# 2_WiFi_Arduino_Pinout.net
KiCad netlist of a schematic drawn in Altium Designer
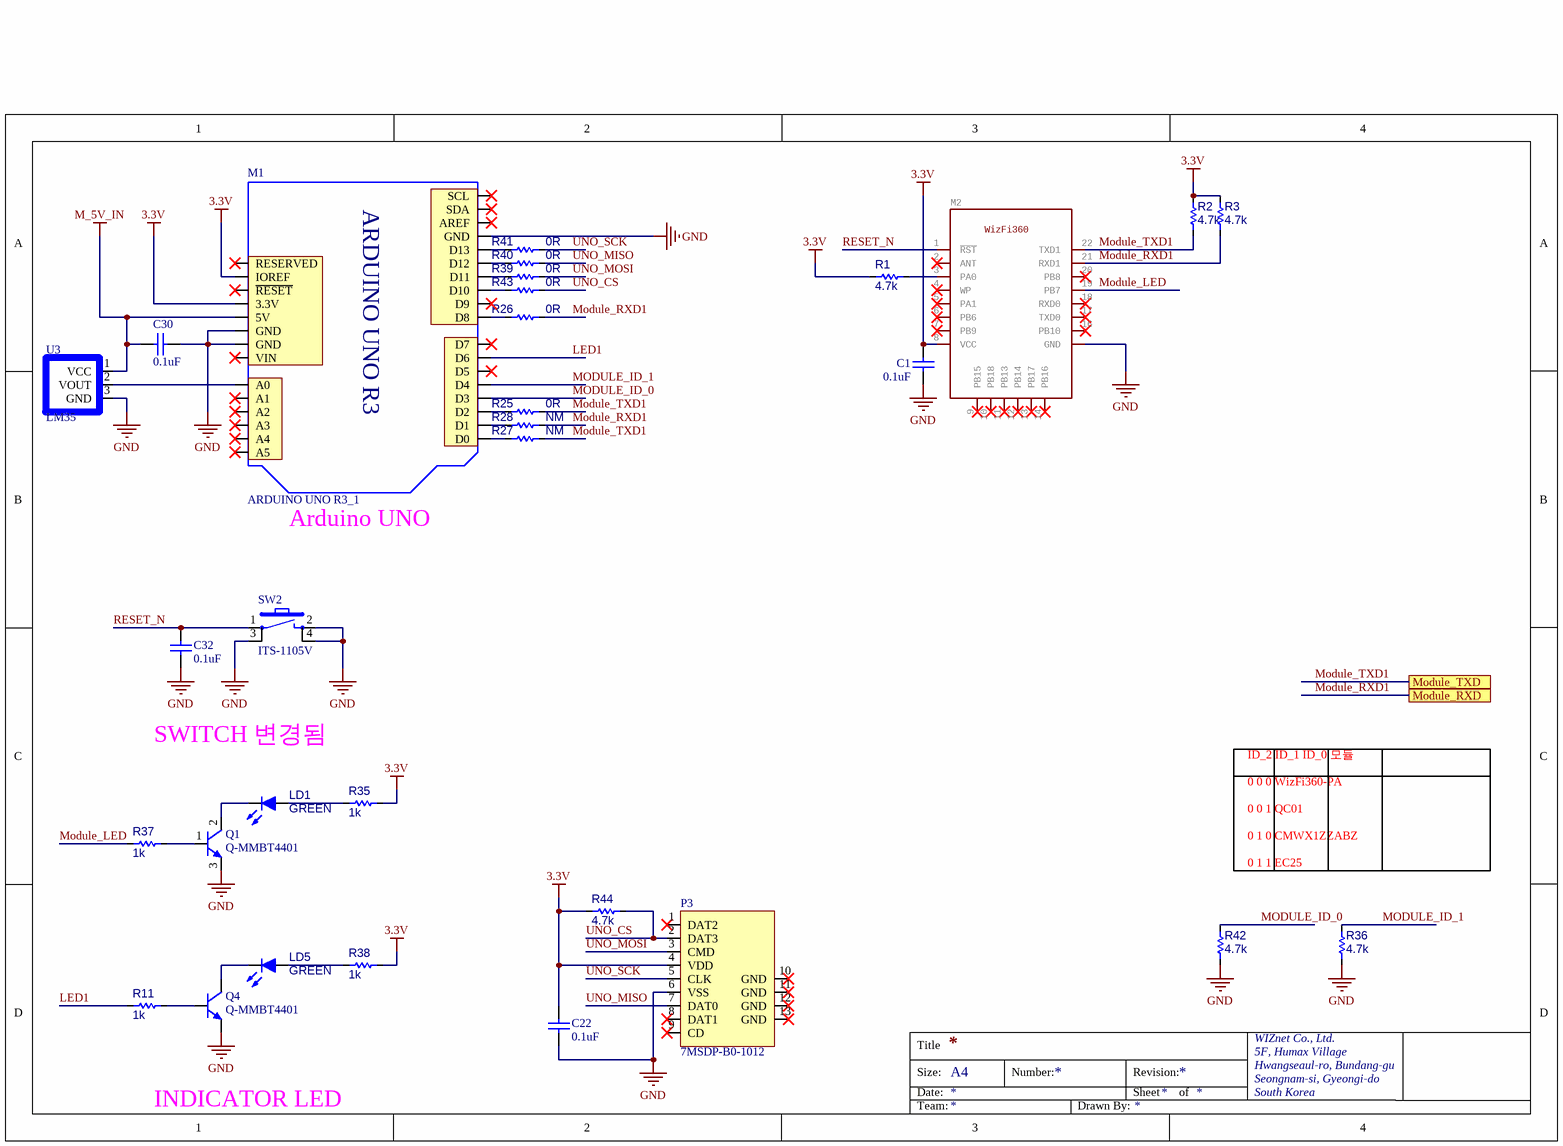
[diagram p0: 2.WiFi_Arduino Pinout.SchDoc]

(export (version "E")
  (design (tool "Eeschema 10.0.6"))
  (components
    (comp (ref "C1")
      (value "0.1uF")
      (footprint "CAP-0402")
      (description "Ceramic CAP 0402(1005)")
      (libsource (lib "Edward") (part "CAP-0402"))
    )
    (comp (ref "C22")
      (value "0.1uF")
      (footprint "CAP-0402")
      (description "Ceramic CAP 0402(1005)")
      (libsource (lib "Edward") (part "CAP-0402"))
    )
    (comp (ref "C30")
      (value "0.1uF")
      (footprint "CAP-0402")
      (description "Ceramic CAP 0402(1005)")
      (libsource (lib "Edward") (part "CAP-0402"))
    )
    (comp (ref "C32")
      (value "0.1uF")
      (footprint "CAP-0402")
      (description "Ceramic CAP 0402(1005)")
      (libsource (lib "Edward") (part "CAP-0402"))
    )
    (comp (ref "LD1")
      (value "GREEN")
      (footprint "LED-0603-GREEN")
      (description "LED-0603")
      (libsource (lib "Scott_lib") (part "LED-0603"))
    )
    (comp (ref "LD5")
      (value "GREEN")
      (footprint "LED-0603-GREEN")
      (description "LED-0603")
      (libsource (lib "Scott_lib") (part "LED-0603"))
    )
    (comp (ref "M1")
      (value "ARDUINO UNO R3_1")
      (footprint "ARDUINOR3_ICSP(3)")
      (description "Arduino UNO R3")
      (libsource (lib "Scott_lib") (part "ARDUINO UNO R3_1"))
    )
    (comp (ref "M2")
      (value "WIZFI360")
      (footprint "WizFi360-PA")
      (fields (field (name "WIZFI360") "WizFi360") (field (name "LIBRARYNAME") "WIZnet"))
      (libsource (lib "WIZnet") (part "WIZFI360"))
    )
    (comp (ref "P3")
      (value "7MSDP-B0-1012")
      (footprint "7MSDP-B0-1012")
      (description "Micro SD Card Socket")
      (libsource (lib "Scott_lib") (part "7MSDP-B0-1012"))
    )
    (comp (ref "Q1")
      (value "Q-MMBT4401")
      (footprint "SOT-23-3LL")
      (description "NPN General-Purpose Amplifier")
      (libsource (lib "Edward") (part "Q-MMBT4401"))
    )
    (comp (ref "Q4")
      (value "Q-MMBT4401")
      (footprint "SOT-23-3LL")
      (description "NPN General-Purpose Amplifier")
      (libsource (lib "") (part "Q-MMBT4401_1"))
    )
    (comp (ref "R1")
      (value "4.7k")
      (footprint "RES-0402")
      (description "RES-0402")
      (libsource (lib "Edward") (part "RES-0402"))
    )
    (comp (ref "R2")
      (value "4.7k")
      (footprint "RES-0402")
      (description "RES-0402")
      (libsource (lib "Edward") (part "RES-0402"))
    )
    (comp (ref "R3")
      (value "4.7k")
      (footprint "RES-0402")
      (description "RES-0402")
      (libsource (lib "Edward") (part "RES-0402"))
    )
    (comp (ref "R11")
      (value "1k")
      (footprint "RES-0402")
      (description "RES-0402")
      (libsource (lib "Edward") (part "RES-0402"))
    )
    (comp (ref "R25")
      (value "0R")
      (footprint "RES-0402")
      (description "RES-0402")
      (libsource (lib "Scott_lib") (part "RES-0402"))
    )
    (comp (ref "R26")
      (value "0R")
      (footprint "RES-0402")
      (description "RES-0402")
      (libsource (lib "Scott_lib") (part "RES-0402"))
    )
    (comp (ref "R27")
      (value "NM")
      (footprint "RES-0402")
      (description "RES-0402")
      (libsource (lib "Scott_lib") (part "RES-0402"))
    )
    (comp (ref "R28")
      (value "NM")
      (footprint "RES-0402")
      (description "RES-0402")
      (libsource (lib "Scott_lib") (part "RES-0402"))
    )
    (comp (ref "R35")
      (value "1k")
      (footprint "RES-0402")
      (description "RES-0402")
      (libsource (lib "Edward") (part "RES-0402"))
    )
    (comp (ref "R36")
      (value "4.7k")
      (footprint "RES-0402")
      (description "RES-0402")
      (libsource (lib "Edward") (part "RES-0402"))
    )
    (comp (ref "R37")
      (value "1k")
      (footprint "RES-0402")
      (description "RES-0402")
      (libsource (lib "Edward") (part "RES-0402"))
    )
    (comp (ref "R38")
      (value "1k")
      (footprint "RES-0402")
      (description "RES-0402")
      (libsource (lib "Edward") (part "RES-0402"))
    )
    (comp (ref "R39")
      (value "0R")
      (footprint "RES-0402")
      (description "RES-0402")
      (libsource (lib "Scott_lib") (part "RES-0402"))
    )
    (comp (ref "R40")
      (value "0R")
      (footprint "RES-0402")
      (description "RES-0402")
      (libsource (lib "Scott_lib") (part "RES-0402"))
    )
    (comp (ref "R41")
      (value "0R")
      (footprint "RES-0402")
      (description "RES-0402")
      (libsource (lib "Scott_lib") (part "RES-0402"))
    )
    (comp (ref "R42")
      (value "4.7k")
      (footprint "RES-0402")
      (description "RES-0402")
      (libsource (lib "Edward") (part "RES-0402"))
    )
    (comp (ref "R43")
      (value "0R")
      (footprint "RES-0402")
      (description "RES-0402")
      (libsource (lib "Scott_lib") (part "RES-0402"))
    )
    (comp (ref "R44")
      (value "4.7k")
      (footprint "RES-0402")
      (description "RES-0402")
      (libsource (lib "Edward") (part "RES-0402"))
    )
    (comp (ref "SW2")
      (value "ITS-1105V")
      (footprint "ITS-1105V(DIP)")
      (description "Angle TACT SW, SMD")
      (libsource (lib "Edward") (part "SWITCH-ANGLE_TACT"))
    )
    (comp (ref "U3") (value "LM35") (footprint "TO-92") (libsource (lib "Edward") (part "LM35")))
  )
  (nets
    (net (code "1") (name "/LED1") (class "Default")
      (node (ref "M1") (pin "D6") (pinfunction "D6_D6") (pintype "passive"))
      (node (ref "R11") (pin "1") (pinfunction "1_1") (pintype "passive"))
    )
    (net (code "2") (name "/MODULE_ID_0") (class "Default")
      (node (ref "M1") (pin "D3") (pinfunction "D3_D3") (pintype "passive"))
      (node (ref "R42") (pin "2") (pinfunction "2_2") (pintype "passive"))
    )
    (net (code "3") (name "/MODULE_ID_1") (class "Default")
      (node (ref "M1") (pin "D4") (pinfunction "D4_D4") (pintype "passive"))
      (node (ref "R36") (pin "2") (pinfunction "2_2") (pintype "passive"))
    )
    (net (code "4") (name "/Module_LED") (class "Default")
      (node (ref "M2") (pin "19") (pinfunction "PB7_19") (pintype "bidirectional"))
      (node (ref "R37") (pin "1") (pinfunction "1_1") (pintype "passive"))
    )
    (net (code "5") (name "/Module_RXD1") (class "Default")
      (node (ref "M2") (pin "21") (pinfunction "RXD1_21") (pintype "passive"))
      (node (ref "R26") (pin "1") (pinfunction "1_1") (pintype "passive"))
      (node (ref "R28") (pin "1") (pinfunction "1_1") (pintype "passive"))
      (node (ref "R3") (pin "2") (pinfunction "2_2") (pintype "passive"))
    )
    (net (code "6") (name "/Module_TXD1") (class "Default")
      (node (ref "M2") (pin "22") (pinfunction "TXD1_22") (pintype "passive"))
      (node (ref "R2") (pin "2") (pinfunction "2_2") (pintype "passive"))
      (node (ref "R25") (pin "1") (pinfunction "1_1") (pintype "passive"))
      (node (ref "R27") (pin "1") (pinfunction "1_1") (pintype "passive"))
    )
    (net (code "7") (name "/RESET_N") (class "Default")
      (node (ref "C32") (pin "2") (pinfunction "2_2") (pintype "passive"))
      (node (ref "M2") (pin "1") (pinfunction "~{RST}_1") (pintype "bidirectional"))
      (node (ref "SW2") (pin "1") (pinfunction "1_1") (pintype "passive"))
    )
    (net (code "8") (name "/UNO_CS") (class "Default")
      (node (ref "P3") (pin "2") (pinfunction "DAT3_2") (pintype "passive"))
      (node (ref "R43") (pin "1") (pinfunction "1_1") (pintype "passive"))
      (node (ref "R44") (pin "1") (pinfunction "1_1") (pintype "passive"))
    )
    (net (code "9") (name "/UNO_MISO") (class "Default")
      (node (ref "P3") (pin "7") (pinfunction "DAT0_7") (pintype "passive"))
      (node (ref "R40") (pin "1") (pinfunction "1_1") (pintype "passive"))
    )
    (net (code "10") (name "/UNO_MOSI") (class "Default")
      (node (ref "P3") (pin "3") (pinfunction "CMD_3") (pintype "passive"))
      (node (ref "R39") (pin "1") (pinfunction "1_1") (pintype "passive"))
    )
    (net (code "11") (name "/UNO_SCK") (class "Default")
      (node (ref "P3") (pin "5") (pinfunction "CLK_5") (pintype "passive"))
      (node (ref "R41") (pin "1") (pinfunction "1_1") (pintype "passive"))
    )
    (net (code "12") (name "3.3V") (class "Default")
      (node (ref "C1") (pin "2") (pinfunction "2_2") (pintype "passive"))
      (node (ref "C22") (pin "1") (pinfunction "1_1") (pintype "passive"))
      (node (ref "M1") (pin "3.3V") (pinfunction "3.3V_3.3V") (pintype "passive"))
      (node (ref "M1") (pin "IOREF") (pinfunction "IOREF_IOREF") (pintype "passive"))
      (node (ref "M2") (pin "8") (pinfunction "VCC_8") (pintype "bidirectional"))
      (node (ref "P3") (pin "4") (pinfunction "VDD_4") (pintype "passive"))
      (node (ref "R1") (pin "2") (pinfunction "2_2") (pintype "passive"))
      (node (ref "R2") (pin "1") (pinfunction "1_1") (pintype "passive"))
      (node (ref "R3") (pin "1") (pinfunction "1_1") (pintype "passive"))
      (node (ref "R35") (pin "2") (pinfunction "2_2") (pintype "passive"))
      (node (ref "R38") (pin "2") (pinfunction "2_2") (pintype "passive"))
      (node (ref "R44") (pin "2") (pinfunction "2_2") (pintype "passive"))
    )
    (net (code "13") (name "GND") (class "Default")
      (node (ref "C1") (pin "1") (pinfunction "1_1") (pintype "passive"))
      (node (ref "C22") (pin "2") (pinfunction "2_2") (pintype "passive"))
      (node (ref "C30") (pin "1") (pinfunction "1_1") (pintype "passive"))
      (node (ref "C32") (pin "1") (pinfunction "1_1") (pintype "passive"))
      (node (ref "M1") (pin "GND1") (pinfunction "GND_GND1") (pintype "passive"))
      (node (ref "M1") (pin "GND2") (pinfunction "GND_GND2") (pintype "passive"))
      (node (ref "M1") (pin "GND4") (pinfunction "GND_GND4") (pintype "passive"))
      (node (ref "M2") (pin "15_23_24") (pinfunction "GND_15_23_24") (pintype "passive"))
      (node (ref "P3") (pin "6") (pinfunction "VSS_6") (pintype "passive"))
      (node (ref "Q1") (pin "3") (pinfunction "E_3") (pintype "passive"))
      (node (ref "Q4") (pin "3") (pinfunction "E_3") (pintype "passive"))
      (node (ref "R36") (pin "1") (pinfunction "1_1") (pintype "passive"))
      (node (ref "R42") (pin "1") (pinfunction "1_1") (pintype "passive"))
      (node (ref "SW2") (pin "2") (pinfunction "2_2") (pintype "passive"))
      (node (ref "SW2") (pin "3") (pinfunction "GND_3") (pintype "passive"))
      (node (ref "SW2") (pin "4") (pinfunction "GND_4") (pintype "passive"))
      (node (ref "U3") (pin "3") (pinfunction "GND_3") (pintype "passive"))
    )
    (net (code "14") (name "M_5V_IN") (class "Default")
      (node (ref "C30") (pin "2") (pinfunction "2_2") (pintype "passive"))
      (node (ref "M1") (pin "5V") (pinfunction "5V_5V") (pintype "passive"))
      (node (ref "U3") (pin "1") (pinfunction "VCC_1") (pintype "passive"))
    )
    (net (code "15") (name "Net-(LD1-A)") (class "Default")
      (node (ref "LD1") (pin "1") (pinfunction "A_1") (pintype "passive"))
      (node (ref "R35") (pin "1") (pinfunction "1_1") (pintype "passive"))
    )
    (net (code "16") (name "Net-(LD1-K)") (class "Default")
      (node (ref "LD1") (pin "2") (pinfunction "K_2") (pintype "passive"))
      (node (ref "Q1") (pin "2") (pinfunction "C_2") (pintype "passive"))
    )
    (net (code "17") (name "Net-(LD5-A)") (class "Default")
      (node (ref "LD5") (pin "1") (pinfunction "A_1") (pintype "passive"))
      (node (ref "R38") (pin "1") (pinfunction "1_1") (pintype "passive"))
    )
    (net (code "18") (name "Net-(LD5-K)") (class "Default")
      (node (ref "LD5") (pin "2") (pinfunction "K_2") (pintype "passive"))
      (node (ref "Q4") (pin "2") (pinfunction "C_2") (pintype "passive"))
    )
    (net (code "19") (name "Net-(M1-PadD0)") (class "Default")
      (node (ref "M1") (pin "D0") (pinfunction "D0_D0") (pintype "passive"))
      (node (ref "R27") (pin "2") (pinfunction "2_2") (pintype "passive"))
    )
    (net (code "20") (name "Net-(M1-PadD1)") (class "Default")
      (node (ref "M1") (pin "D1") (pinfunction "D1_D1") (pintype "passive"))
      (node (ref "R28") (pin "2") (pinfunction "2_2") (pintype "passive"))
    )
    (net (code "21") (name "Net-(M1-PadD2)") (class "Default")
      (node (ref "M1") (pin "D2") (pinfunction "D2_D2") (pintype "passive"))
      (node (ref "R25") (pin "2") (pinfunction "2_2") (pintype "passive"))
    )
    (net (code "22") (name "Net-(M1-PadD8)") (class "Default")
      (node (ref "M1") (pin "D8") (pinfunction "D8_D8") (pintype "passive"))
      (node (ref "R26") (pin "2") (pinfunction "2_2") (pintype "passive"))
    )
    (net (code "23") (name "Net-(M1-PadD10)") (class "Default")
      (node (ref "M1") (pin "D10") (pinfunction "D10_D10") (pintype "passive"))
      (node (ref "R43") (pin "2") (pinfunction "2_2") (pintype "passive"))
    )
    (net (code "24") (name "Net-(M1-PadD11)") (class "Default")
      (node (ref "M1") (pin "D11") (pinfunction "D11_D11") (pintype "passive"))
      (node (ref "R39") (pin "2") (pinfunction "2_2") (pintype "passive"))
    )
    (net (code "25") (name "Net-(M1-PadD12)") (class "Default")
      (node (ref "M1") (pin "D12") (pinfunction "D12_D12") (pintype "passive"))
      (node (ref "R40") (pin "2") (pinfunction "2_2") (pintype "passive"))
    )
    (net (code "26") (name "Net-(M1-PadD13)") (class "Default")
      (node (ref "M1") (pin "D13") (pinfunction "D13_D13") (pintype "passive"))
      (node (ref "R41") (pin "2") (pinfunction "2_2") (pintype "passive"))
    )
    (net (code "27") (name "Net-(M2-PA0)") (class "Default")
      (node (ref "M2") (pin "3") (pinfunction "PA0_3") (pintype "bidirectional"))
      (node (ref "R1") (pin "1") (pinfunction "1_1") (pintype "passive"))
    )
    (net (code "28") (name "Net-(Q1-B)") (class "Default")
      (node (ref "Q1") (pin "1") (pinfunction "B_1") (pintype "passive"))
      (node (ref "R37") (pin "2") (pinfunction "2_2") (pintype "passive"))
    )
    (net (code "29") (name "Net-(Q4-B)") (class "Default")
      (node (ref "Q4") (pin "1") (pinfunction "B_1") (pintype "passive"))
      (node (ref "R11") (pin "2") (pinfunction "2_2") (pintype "passive"))
    )
    (net (code "30") (name "Net-(U3-VOUT)") (class "Default")
      (node (ref "M1") (pin "A0") (pinfunction "A0_A0") (pintype "passive"))
      (node (ref "U3") (pin "2") (pinfunction "VOUT_2") (pintype "passive"))
    )
    (net (code "31") (name "unconnected-(M1-PadA1)") (class "Default")
      (node (ref "M1") (pin "A1") (pinfunction "A1_A1") (pintype "passive+no_connect"))
    )
    (net (code "32") (name "unconnected-(M1-PadA2)") (class "Default")
      (node (ref "M1") (pin "A2") (pinfunction "A2_A2") (pintype "passive+no_connect"))
    )
    (net (code "33") (name "unconnected-(M1-PadA3)") (class "Default")
      (node (ref "M1") (pin "A3") (pinfunction "A3_A3") (pintype "passive+no_connect"))
    )
    (net (code "34") (name "unconnected-(M1-PadA4)") (class "Default")
      (node (ref "M1") (pin "A4") (pinfunction "A4_A4") (pintype "passive+no_connect"))
    )
    (net (code "35") (name "unconnected-(M1-PadA5)") (class "Default")
      (node (ref "M1") (pin "A5") (pinfunction "A5_A5") (pintype "passive+no_connect"))
    )
    (net (code "36") (name "unconnected-(M1-PadAREF)") (class "Default")
      (node (ref "M1") (pin "AREF") (pinfunction "AREF_AREF") (pintype "passive+no_connect"))
    )
    (net (code "37") (name "unconnected-(M1-PadD5)") (class "Default")
      (node (ref "M1") (pin "D5") (pinfunction "D5_D5") (pintype "passive+no_connect"))
    )
    (net (code "38") (name "unconnected-(M1-PadD7)") (class "Default")
      (node (ref "M1") (pin "D7") (pinfunction "D7_D7") (pintype "passive+no_connect"))
    )
    (net (code "39") (name "unconnected-(M1-PadD9)") (class "Default")
      (node (ref "M1") (pin "D9") (pinfunction "D9_D9") (pintype "passive+no_connect"))
    )
    (net (code "40") (name "unconnected-(M1-PadRESERVED)") (class "Default")
      (node (ref "M1") (pin "RESERVED") (pinfunction "RESERVED_RESERVED") (pintype "passive+no_connect"))
    )
    (net (code "41") (name "unconnected-(M1-PadRESET)") (class "Default")
      (node (ref "M1") (pin "RESET") (pinfunction "RESET_RESET") (pintype "passive+no_connect"))
    )
    (net (code "42") (name "unconnected-(M1-PadSCL)") (class "Default")
      (node (ref "M1") (pin "SCL") (pinfunction "SCL_SCL") (pintype "passive+no_connect"))
    )
    (net (code "43") (name "unconnected-(M1-PadSDA)") (class "Default")
      (node (ref "M1") (pin "SDA") (pinfunction "SDA_SDA") (pintype "passive+no_connect"))
    )
    (net (code "44") (name "unconnected-(M1-PadVIN)") (class "Default")
      (node (ref "M1") (pin "VIN") (pinfunction "VIN_VIN") (pintype "passive+no_connect"))
    )
    (net (code "45") (name "unconnected-(M2-ANT-Pad2)") (class "Default")
      (node (ref "M2") (pin "2") (pinfunction "ANT_2") (pintype "bidirectional+no_connect"))
    )
    (net (code "46") (name "unconnected-(M2-PA1-Pad5)") (class "Default")
      (node (ref "M2") (pin "5") (pinfunction "PA1_5") (pintype "bidirectional+no_connect"))
    )
    (net (code "47") (name "unconnected-(M2-PB6-Pad6)") (class "Default")
      (node (ref "M2") (pin "6") (pinfunction "PB6_6") (pintype "bidirectional+no_connect"))
    )
    (net (code "48") (name "unconnected-(M2-PB8-Pad20)") (class "Default")
      (node (ref "M2") (pin "20") (pinfunction "PB8_20") (pintype "bidirectional+no_connect"))
    )
    (net (code "49") (name "unconnected-(M2-PB9-Pad7)") (class "Default")
      (node (ref "M2") (pin "7") (pinfunction "PB9_7") (pintype "bidirectional+no_connect"))
    )
    (net (code "50") (name "unconnected-(M2-PB10-Pad16)") (class "Default")
      (node (ref "M2") (pin "16") (pinfunction "PB10_16") (pintype "bidirectional+no_connect"))
    )
    (net (code "51") (name "unconnected-(M2-PB13-Pad11)") (class "Default")
      (node (ref "M2") (pin "11") (pinfunction "PB13_11") (pintype "bidirectional+no_connect"))
    )
    (net (code "52") (name "unconnected-(M2-PB14-Pad12)") (class "Default")
      (node (ref "M2") (pin "12") (pinfunction "PB14_12") (pintype "bidirectional+no_connect"))
    )
    (net (code "53") (name "unconnected-(M2-PB15-Pad9)") (class "Default")
      (node (ref "M2") (pin "9") (pinfunction "PB15_9") (pintype "bidirectional+no_connect"))
    )
    (net (code "54") (name "unconnected-(M2-PB16-Pad14)") (class "Default")
      (node (ref "M2") (pin "14") (pinfunction "PB16_14") (pintype "bidirectional+no_connect"))
    )
    (net (code "55") (name "unconnected-(M2-PB17-Pad13)") (class "Default")
      (node (ref "M2") (pin "13") (pinfunction "PB17_13") (pintype "bidirectional+no_connect"))
    )
    (net (code "56") (name "unconnected-(M2-PB18-Pad10)") (class "Default")
      (node (ref "M2") (pin "10") (pinfunction "PB18_10") (pintype "bidirectional+no_connect"))
    )
    (net (code "57") (name "unconnected-(M2-RXD0-Pad18)") (class "Default")
      (node (ref "M2") (pin "18") (pinfunction "RXD0_18") (pintype "passive+no_connect"))
    )
    (net (code "58") (name "unconnected-(M2-TXD0-Pad17)") (class "Default")
      (node (ref "M2") (pin "17") (pinfunction "TXD0_17") (pintype "passive+no_connect"))
    )
    (net (code "59") (name "unconnected-(M2-WP-Pad4)") (class "Default")
      (node (ref "M2") (pin "4") (pinfunction "WP_4") (pintype "bidirectional+no_connect"))
    )
    (net (code "60") (name "unconnected-(P3-CD-Pad9)") (class "Default")
      (node (ref "P3") (pin "9") (pinfunction "CD_9") (pintype "passive+no_connect"))
    )
    (net (code "61") (name "unconnected-(P3-DAT1-Pad8)") (class "Default")
      (node (ref "P3") (pin "8") (pinfunction "DAT1_8") (pintype "passive+no_connect"))
    )
    (net (code "62") (name "unconnected-(P3-DAT2-Pad1)") (class "Default")
      (node (ref "P3") (pin "1") (pinfunction "DAT2_1") (pintype "passive+no_connect"))
    )
    (net (code "63") (name "unconnected-(P3-GND-Pad10)") (class "Default")
      (node (ref "P3") (pin "10") (pinfunction "GND_10") (pintype "passive+no_connect"))
    )
    (net (code "64") (name "unconnected-(P3-GND-Pad11)") (class "Default")
      (node (ref "P3") (pin "11") (pinfunction "GND_11") (pintype "passive+no_connect"))
    )
    (net (code "65") (name "unconnected-(P3-GND-Pad12)") (class "Default")
      (node (ref "P3") (pin "12") (pinfunction "GND_12") (pintype "passive+no_connect"))
    )
    (net (code "66") (name "unconnected-(P3-GND-Pad13)") (class "Default")
      (node (ref "P3") (pin "13") (pinfunction "GND_13") (pintype "passive+no_connect"))
    )
  )
)
